# ProPrj_11_dc_2024-12-13.net
KiCad netlist of a schematic drawn in EasyEDA Pro
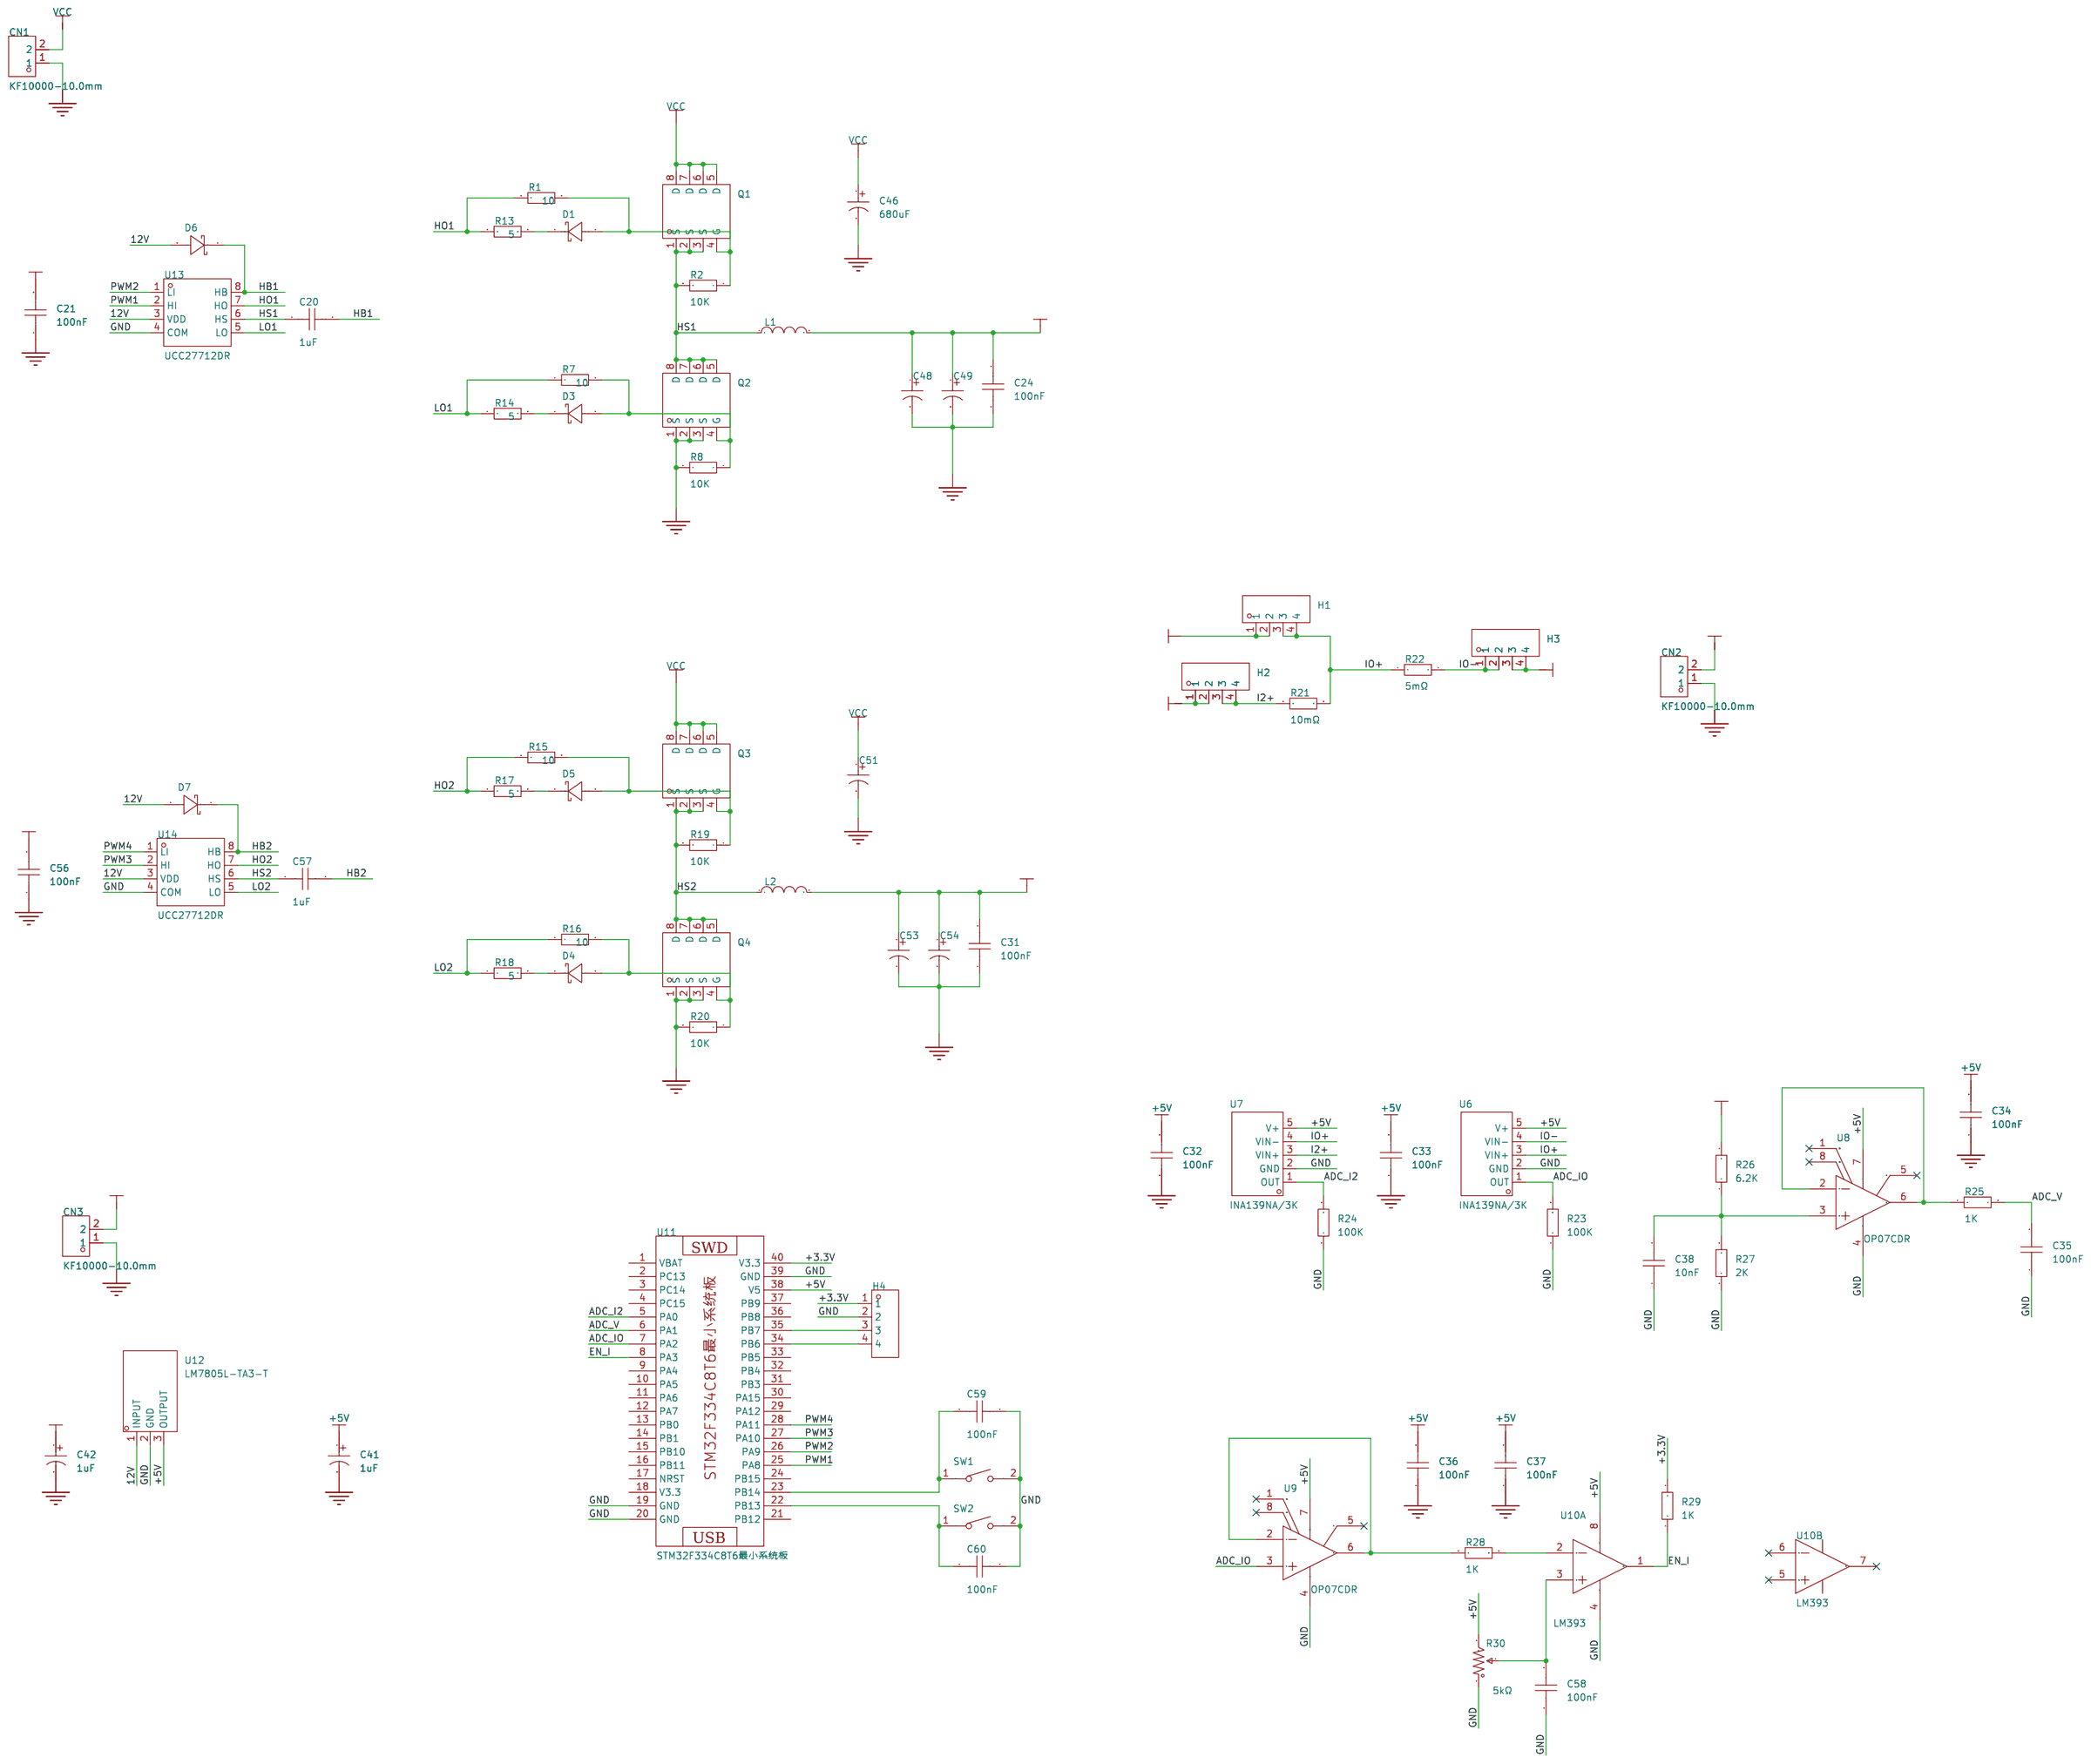
[diagram p0: schematic sheet]

(export (version "E")
  (design (tool "Eeschema 10.0.6"))
  (components
    (comp (ref "C20")
      (value "1uF")
      (footprint "easyedapro:C0603")
      (libsource (lib "easyedapro") (part "CapAcitance"))
    )
    (comp (ref "C21")
      (value "100nF")
      (footprint "easyedapro:C0603")
      (libsource (lib "easyedapro") (part "CapAcitance"))
    )
    (comp (ref "C24")
      (value "100nF")
      (footprint "easyedapro:C0603")
      (libsource (lib "easyedapro") (part "CapAcitance"))
    )
    (comp (ref "C31")
      (value "100nF")
      (footprint "easyedapro:C0603")
      (libsource (lib "easyedapro") (part "CapAcitance"))
    )
    (comp (ref "C32")
      (value "100nF")
      (footprint "easyedapro:C0603")
      (libsource (lib "easyedapro") (part "CapAcitance"))
    )
    (comp (ref "C33")
      (value "100nF")
      (footprint "easyedapro:C0603")
      (libsource (lib "easyedapro") (part "CapAcitance"))
    )
    (comp (ref "C34")
      (value "100nF")
      (footprint "easyedapro:C0603")
      (libsource (lib "easyedapro") (part "CapAcitance"))
    )
    (comp (ref "C35")
      (value "100nF")
      (footprint "easyedapro:C0603")
      (libsource (lib "easyedapro") (part "CapAcitance"))
    )
    (comp (ref "C36")
      (value "100nF")
      (footprint "easyedapro:C0603")
      (libsource (lib "easyedapro") (part "CapAcitance"))
    )
    (comp (ref "C37")
      (value "100nF")
      (footprint "easyedapro:C0603")
      (libsource (lib "easyedapro") (part "CapAcitance"))
    )
    (comp (ref "C38")
      (value "10nF")
      (footprint "easyedapro:C0603")
      (libsource (lib "easyedapro") (part "CapAcitance"))
    )
    (comp (ref "C41")
      (value "1uF")
      (footprint "easyedapro:CAP-TH_BD5.0-P2.00-D0.8-FD")
      (description "容值:1uF;精度:±20%;额定电压:50V;")
      (fields (field (name "Manufacturer Part") "KF010M050C110A") (field (name "Manufacturer") "CapXon(丰宾)"))
      (libsource (lib "easyedapro") (part "KF010M050C110A"))
    )
    (comp (ref "C42")
      (value "1uF")
      (footprint "easyedapro:CAP-TH_BD5.0-P2.00-D0.8-FD")
      (description "容值:1uF;精度:±20%;额定电压:50V;")
      (fields (field (name "Manufacturer Part") "KF010M050C110A") (field (name "Manufacturer") "CapXon(丰宾)"))
      (libsource (lib "easyedapro") (part "KF010M050C110A"))
    )
    (comp (ref "C46")
      (value "680uF")
      (footprint "easyedapro:CAP-TH_BD12.5-P5.00-D0.6-FD")
      (description "容值:680uF;精度:±20%;额定电压:63V;")
      (fields (field (name "Manufacturer Part") "ERR1JM681W25OT") (field (name "Manufacturer") "AISHI(艾华集团)"))
      (libsource (lib "easyedapro") (part "ERR1JM681W25OT"))
    )
    (comp (ref "C48")
      (value "680uF")
      (footprint "easyedapro:CAP-TH_BD12.5-P5.00-D0.6-FD")
      (description "容值:680uF;精度:±20%;额定电压:63V;")
      (fields (field (name "Manufacturer Part") "ERR1JM681W25OT") (field (name "Manufacturer") "AISHI(艾华集团)"))
      (libsource (lib "easyedapro") (part "ERR1JM681W25OT"))
    )
    (comp (ref "C49")
      (value "680uF")
      (footprint "easyedapro:CAP-TH_BD12.5-P5.00-D0.6-FD")
      (description "容值:680uF;精度:±20%;额定电压:63V;")
      (fields (field (name "Manufacturer Part") "ERR1JM681W25OT") (field (name "Manufacturer") "AISHI(艾华集团)"))
      (libsource (lib "easyedapro") (part "ERR1JM681W25OT"))
    )
    (comp (ref "C51")
      (value "680uF")
      (footprint "easyedapro:CAP-TH_BD12.5-P5.00-D0.6-FD")
      (description "容值:680uF;精度:±20%;额定电压:63V;")
      (fields (field (name "Manufacturer Part") "ERR1JM681W25OT") (field (name "Manufacturer") "AISHI(艾华集团)"))
      (libsource (lib "easyedapro") (part "ERR1JM681W25OT"))
    )
    (comp (ref "C53")
      (value "680uF")
      (footprint "easyedapro:CAP-TH_BD12.5-P5.00-D0.6-FD")
      (description "容值:680uF;精度:±20%;额定电压:63V;")
      (fields (field (name "Manufacturer Part") "ERR1JM681W25OT") (field (name "Manufacturer") "AISHI(艾华集团)"))
      (libsource (lib "easyedapro") (part "ERR1JM681W25OT"))
    )
    (comp (ref "C54")
      (value "680uF")
      (footprint "easyedapro:CAP-TH_BD12.5-P5.00-D0.6-FD")
      (description "容值:680uF;精度:±20%;额定电压:63V;")
      (fields (field (name "Manufacturer Part") "ERR1JM681W25OT") (field (name "Manufacturer") "AISHI(艾华集团)"))
      (libsource (lib "easyedapro") (part "ERR1JM681W25OT"))
    )
    (comp (ref "C56")
      (value "100nF")
      (footprint "easyedapro:C0603")
      (libsource (lib "easyedapro") (part "CapAcitance"))
    )
    (comp (ref "C57")
      (value "1uF")
      (footprint "easyedapro:C0603")
      (libsource (lib "easyedapro") (part "CapAcitance"))
    )
    (comp (ref "C58")
      (value "100nF")
      (footprint "easyedapro:C0603")
      (libsource (lib "easyedapro") (part "CapAcitance"))
    )
    (comp (ref "C59")
      (value "100nF")
      (footprint "easyedapro:C0603")
      (libsource (lib "easyedapro") (part "CapAcitance"))
    )
    (comp (ref "C60")
      (value "100nF")
      (footprint "easyedapro:C0603")
      (libsource (lib "easyedapro") (part "CapAcitance"))
    )
    (comp (ref "CN1")
      (value "KF10000-10.0mm")
      (footprint "easyedapro:CONN-TH_2P-P10.00_KF10000-10.0MM")
      (libsource (lib "easyedapro") (part "KF10000-10.0MM_C9900018859"))
    )
    (comp (ref "CN2")
      (value "KF10000-10.0mm")
      (footprint "easyedapro:CONN-TH_2P-P10.00_KF10000-10.0MM")
      (libsource (lib "easyedapro") (part "KF10000-10.0MM_C9900018859"))
    )
    (comp (ref "CN3")
      (value "KF10000-10.0mm")
      (footprint "easyedapro:CONN-TH_2P-P10.00_KF10000-10.0MM")
      (libsource (lib "easyedapro") (part "KF10000-10.0MM_C9900018859"))
    )
    (comp (ref "D1")
      (value "1N5819WS S4")
      (footprint "easyedapro:SOD-323_L1.6-W1.3-LS2.7-RD")
      (description "二极管配置:独立式;正向压降(Vf):600mV@200mA;直流反向耐压(Vr):40V;平均整流电流(Io):350mA;")
      (fields (field (name "Manufacturer") "JSMSEMI(杰盛微)"))
      (libsource (lib "easyedapro") (part "1N5819WS S4"))
    )
    (comp (ref "D3")
      (value "1N5819WS S4")
      (footprint "easyedapro:SOD-323_L1.6-W1.3-LS2.7-RD")
      (description "二极管配置:独立式;正向压降(Vf):600mV@200mA;直流反向耐压(Vr):40V;平均整流电流(Io):350mA;")
      (fields (field (name "Manufacturer") "JSMSEMI(杰盛微)"))
      (libsource (lib "easyedapro") (part "1N5819WS S4"))
    )
    (comp (ref "D4")
      (value "1N5819WS S4")
      (footprint "easyedapro:SOD-323_L1.6-W1.3-LS2.7-RD")
      (description "二极管配置:独立式;正向压降(Vf):600mV@200mA;直流反向耐压(Vr):40V;平均整流电流(Io):350mA;")
      (fields (field (name "Manufacturer") "JSMSEMI(杰盛微)"))
      (libsource (lib "easyedapro") (part "1N5819WS S4"))
    )
    (comp (ref "D5")
      (value "1N5819WS S4")
      (footprint "easyedapro:SOD-323_L1.6-W1.3-LS2.7-RD")
      (description "二极管配置:独立式;正向压降(Vf):600mV@200mA;直流反向耐压(Vr):40V;平均整流电流(Io):350mA;")
      (fields (field (name "Manufacturer") "JSMSEMI(杰盛微)"))
      (libsource (lib "easyedapro") (part "1N5819WS S4"))
    )
    (comp (ref "D6")
      (value "1N5819WS S4")
      (footprint "easyedapro:SOD-323_L1.6-W1.3-LS2.7-RD")
      (description "二极管配置:独立式;正向压降(Vf):600mV@200mA;直流反向耐压(Vr):40V;平均整流电流(Io):350mA;")
      (fields (field (name "Manufacturer") "JSMSEMI(杰盛微)"))
      (libsource (lib "easyedapro") (part "1N5819WS S4"))
    )
    (comp (ref "D7")
      (value "1N5819WS S4")
      (footprint "easyedapro:SOD-323_L1.6-W1.3-LS2.7-RD")
      (description "二极管配置:独立式;正向压降(Vf):600mV@200mA;直流反向耐压(Vr):40V;平均整流电流(Io):350mA;")
      (fields (field (name "Manufacturer") "JSMSEMI(杰盛微)"))
      (libsource (lib "easyedapro") (part "1N5819WS S4"))
    )
    (comp (ref "H1")
      (value "~")
      (footprint "easyedapro:HDR-TH_4P-P2.54-V-M")
      (libsource (lib "easyedapro") (part "PZ254V-11-04P"))
    )
    (comp (ref "H2")
      (value "~")
      (footprint "easyedapro:HDR-TH_4P-P2.54-V-M")
      (libsource (lib "easyedapro") (part "PZ254V-11-04P"))
    )
    (comp (ref "H3")
      (value "~")
      (footprint "easyedapro:HDR-TH_4P-P2.54-V-M")
      (libsource (lib "easyedapro") (part "PZ254V-11-04P"))
    )
    (comp (ref "H4")
      (value "~")
      (footprint "easyedapro:HDR-TH_4P-P2.54-V-M")
      (libsource (lib "easyedapro") (part "PZ254V-11-04P"))
    )
    (comp (ref "L1")
      (value "L-SMD1010-PCB")
      (footprint "easyedapro:IND-SMD_L10.0-W10.0-2")
      (libsource (lib "easyedapro") (part "L-SMD1010-PCB_C9900024506"))
    )
    (comp (ref "L2")
      (value "L-SMD1010-PCB")
      (footprint "easyedapro:IND-SMD_L10.0-W10.0-2")
      (libsource (lib "easyedapro") (part "L-SMD1010-PCB_C9900024506"))
    )
    (comp (ref "Q1")
      (value "CSD18540Q5BT")
      (footprint "easyedapro:PDFNWB-8L_L6.0-W5.0-P1.27-BL-EP")
      (description "60V、N 通道 NexFET&#153; 功率 MOSFET 8-VSON-CLIP -55 to 175")
      (fields (field (name "Manufacturer") "TI(德州仪器)"))
      (libsource (lib "easyedapro") (part "CSD18540Q5BT"))
    )
    (comp (ref "Q2")
      (value "CSD18540Q5BT")
      (footprint "easyedapro:PDFNWB-8L_L6.0-W5.0-P1.27-BL-EP")
      (description "60V、N 通道 NexFET&#153; 功率 MOSFET 8-VSON-CLIP -55 to 175")
      (fields (field (name "Manufacturer") "TI(德州仪器)"))
      (libsource (lib "easyedapro") (part "CSD18540Q5BT"))
    )
    (comp (ref "Q3")
      (value "CSD18540Q5BT")
      (footprint "easyedapro:PDFNWB-8L_L6.0-W5.0-P1.27-BL-EP")
      (description "60V、N 通道 NexFET&#153; 功率 MOSFET 8-VSON-CLIP -55 to 175")
      (fields (field (name "Manufacturer") "TI(德州仪器)"))
      (libsource (lib "easyedapro") (part "CSD18540Q5BT"))
    )
    (comp (ref "Q4")
      (value "CSD18540Q5BT")
      (footprint "easyedapro:PDFNWB-8L_L6.0-W5.0-P1.27-BL-EP")
      (description "60V、N 通道 NexFET&#153; 功率 MOSFET 8-VSON-CLIP -55 to 175")
      (fields (field (name "Manufacturer") "TI(德州仪器)"))
      (libsource (lib "easyedapro") (part "CSD18540Q5BT"))
    )
    (comp (ref "R1") (value "10") (footprint "easyedapro:R1206") (libsource (lib "easyedapro") (part "电阻")))
    (comp (ref "R2") (value "10K") (footprint "easyedapro:R1206") (libsource (lib "easyedapro") (part "电阻")))
    (comp (ref "R7") (value "10") (footprint "easyedapro:R1206") (libsource (lib "easyedapro") (part "电阻")))
    (comp (ref "R8") (value "10K") (footprint "easyedapro:R1206") (libsource (lib "easyedapro") (part "电阻")))
    (comp (ref "R13") (value "5") (footprint "easyedapro:R1206") (libsource (lib "easyedapro") (part "电阻")))
    (comp (ref "R14") (value "5") (footprint "easyedapro:R1206") (libsource (lib "easyedapro") (part "电阻")))
    (comp (ref "R15") (value "10") (footprint "easyedapro:R1206") (libsource (lib "easyedapro") (part "电阻")))
    (comp (ref "R16") (value "10") (footprint "easyedapro:R1206") (libsource (lib "easyedapro") (part "电阻")))
    (comp (ref "R17") (value "5") (footprint "easyedapro:R1206") (libsource (lib "easyedapro") (part "电阻")))
    (comp (ref "R18") (value "5") (footprint "easyedapro:R1206") (libsource (lib "easyedapro") (part "电阻")))
    (comp (ref "R19") (value "10K") (footprint "easyedapro:R1206") (libsource (lib "easyedapro") (part "电阻")))
    (comp (ref "R20") (value "10K") (footprint "easyedapro:R1206") (libsource (lib "easyedapro") (part "电阻")))
    (comp (ref "R21")
      (value "10mΩ")
      (footprint "easyedapro:R1206")
      (libsource (lib "easyedapro") (part "电阻"))
    )
    (comp (ref "R22") (value "5mΩ") (footprint "easyedapro:R1206") (libsource (lib "easyedapro") (part "电阻")))
    (comp (ref "R23")
      (value "100K")
      (footprint "easyedapro:R1206")
      (libsource (lib "easyedapro") (part "电阻"))
    )
    (comp (ref "R24")
      (value "100K")
      (footprint "easyedapro:R1206")
      (libsource (lib "easyedapro") (part "电阻"))
    )
    (comp (ref "R25") (value "1K") (footprint "easyedapro:R1206") (libsource (lib "easyedapro") (part "电阻")))
    (comp (ref "R26")
      (value "6.2K")
      (footprint "easyedapro:R1206")
      (libsource (lib "easyedapro") (part "电阻"))
    )
    (comp (ref "R27") (value "2K") (footprint "easyedapro:R1206") (libsource (lib "easyedapro") (part "电阻")))
    (comp (ref "R28") (value "1K") (footprint "easyedapro:R1206") (libsource (lib "easyedapro") (part "电阻")))
    (comp (ref "R29") (value "1K") (footprint "easyedapro:R1206") (libsource (lib "easyedapro") (part "电阻")))
    (comp (ref "R30")
      (value "5kΩ")
      (footprint "easyedapro:RES-ADJ-TH_3P-L9.5-W4.85-P2.50-BL-BS")
      (description "阻值:5kΩ;精度:±10%;")
      (fields (field (name "Manufacturer Part") "3296W-1-502") (field (name "Manufacturer") "BOCHEN(博晨)"))
      (libsource (lib "easyedapro") (part "3296W-1-502"))
    )
    (comp (ref "SW1")
      (value "轻触按键3*4*H")
      (footprint "easyedapro:SW-SMD_L4.0-W2.9-LS5.0")
      (libsource (lib "easyedapro") (part "轻触按键3*4*H"))
    )
    (comp (ref "SW2")
      (value "轻触按键3*4*H")
      (footprint "easyedapro:SW-SMD_L4.0-W2.9-LS5.0")
      (libsource (lib "easyedapro") (part "轻触按键3*4*H"))
    )
    (comp (ref "U6")
      (value "INA139NA/3K")
      (footprint "easyedapro:SOT-23-5_L3.0-W1.7-P0.95-LS2.8-BR")
      (description "INA139 36V、高侧、高速、电流输出电流分流监控器")
      (fields (field (name "Manufacturer") "TI(德州仪器)"))
      (libsource (lib "easyedapro") (part "INA139NA/3K"))
    )
    (comp (ref "U7")
      (value "INA139NA/3K")
      (footprint "easyedapro:SOT-23-5_L3.0-W1.7-P0.95-LS2.8-BR")
      (description "INA139 36V、高侧、高速、电流输出电流分流监控器")
      (fields (field (name "Manufacturer") "TI(德州仪器)"))
      (libsource (lib "easyedapro") (part "INA139NA/3K"))
    )
    (comp (ref "U8")
      (value "OP07CDR")
      (footprint "easyedapro:SOIC-8_L4.9-W3.9-P1.27-LS6.0-BL")
      (description "放大器数:单路;增益带宽积(GBP):600kHz;输入偏置电流(Ib):1.8nA;压摆率(SR):0.3V/us;轨到轨:-;")
      (fields (field (name "Manufacturer") "TI(德州仪器)"))
      (libsource (lib "easyedapro") (part "OP07CDR"))
    )
    (comp (ref "U9")
      (value "OP07CDR")
      (footprint "easyedapro:SOIC-8_L4.9-W3.9-P1.27-LS6.0-BL")
      (description "放大器数:单路;增益带宽积(GBP):600kHz;输入偏置电流(Ib):1.8nA;压摆率(SR):0.3V/us;轨到轨:-;")
      (fields (field (name "Manufacturer") "TI(德州仪器)"))
      (libsource (lib "easyedapro") (part "OP07CDR"))
    )
    (comp (ref "U10")
      (value "LM393")
      (footprint "easyedapro:SOP-8_L4.9-W3.9-P1.27-LS6.0-BL")
      (description "输入失调电压(Vos):3mV;输入偏置电流(Ib):-;轨到轨:-;")
      (fields (field (name "Manufacturer") "IDCHIP(英锐芯)"))
      (libsource (lib "easyedapro") (part "LM393_C400839"))
    )
    (comp (ref "U11")
      (value "STM32F334C8T6最小系统板")
      (footprint "easyedapro:STM32F103C8T6核心板")
      (fields (field (name "Manufacturer Part") "STM32F103C8T6最小系统模块") (field (name "Manufacturer") "无"))
      (libsource (lib "easyedapro") (part "STM32F103C8T6最小系统板"))
    )
    (comp (ref "U12")
      (value "LM7805L-TA3-T")
      (footprint "easyedapro:TO-220IS_L10.16-W4.7-P2.54-L")
      (description "输出类型:-;")
      (libsource (lib "easyedapro") (part "LM7805L-TA3-T_C340686"))
    )
    (comp (ref "U13")
      (value "UCC27712DR")
      (footprint "easyedapro:SOIC-8_L4.9-W3.9-P1.27-LS6.0-BL")
      (description "驱动配置:半桥;负载类型:MOSFET；IGBT;驱动通道数:2;峰值灌电流:2.8A;峰值拉电流:1.8A;电源电压:10V~20V;上升时间:16ns;下降时间:10ns;")
      (fields (field (name "Manufacturer") "TI(德州仪器)"))
      (libsource (lib "easyedapro") (part "UCC27712DR"))
    )
    (comp (ref "U14")
      (value "UCC27712DR")
      (footprint "easyedapro:SOIC-8_L4.9-W3.9-P1.27-LS6.0-BL")
      (description "驱动配置:半桥;负载类型:MOSFET；IGBT;驱动通道数:2;峰值灌电流:2.8A;峰值拉电流:1.8A;电源电压:10V~20V;上升时间:16ns;下降时间:10ns;")
      (fields (field (name "Manufacturer") "TI(德州仪器)"))
      (libsource (lib "easyedapro") (part "UCC27712DR"))
    )
  )
  (nets
    (net (code "1") (name "+5V") (class "Default")
      (node (ref "C32") (pin "2") (pinfunction "2_2") (pintype "input"))
      (node (ref "C33") (pin "2") (pinfunction "2_2") (pintype "input"))
      (node (ref "C34") (pin "2") (pinfunction "2_2") (pintype "input"))
      (node (ref "C36") (pin "2") (pinfunction "2_2") (pintype "input"))
      (node (ref "C37") (pin "2") (pinfunction "2_2") (pintype "input"))
      (node (ref "C41") (pin "1") (pinfunction "1_1") (pintype "input"))
      (node (ref "R30") (pin "3") (pinfunction "3_3") (pintype "unspecified"))
      (node (ref "U10") (pin "8") (pinfunction "VCC_8") (pintype "unspecified"))
      (node (ref "U11") (pin "38") (pinfunction "V5_38") (pintype "input"))
      (node (ref "U12") (pin "3") (pinfunction "OUTPUT_3") (pintype "unspecified"))
      (node (ref "U6") (pin "5") (pinfunction "V+_5") (pintype "unspecified"))
      (node (ref "U7") (pin "5") (pinfunction "V+_5") (pintype "unspecified"))
      (node (ref "U8") (pin "7") (pinfunction "VCC+_7") (pintype "unspecified"))
      (node (ref "U9") (pin "7") (pinfunction "VCC+_7") (pintype "unspecified"))
    )
    (net (code "2") (name "/+3.3V") (class "Default")
      (node (ref "H4") (pin "1") (pinfunction "1_1") (pintype "unspecified"))
      (node (ref "R29") (pin "2") (pinfunction "2_2") (pintype "input"))
      (node (ref "U11") (pin "40") (pinfunction "V3.3_40") (pintype "input"))
    )
    (net (code "3") (name "/ADC_I2") (class "Default")
      (node (ref "R24") (pin "2") (pinfunction "2_2") (pintype "input"))
      (node (ref "U11") (pin "5") (pinfunction "PA0_5") (pintype "bidirectional"))
      (node (ref "U7") (pin "1") (pinfunction "OUT_1") (pintype "unspecified"))
    )
    (net (code "4") (name "/ADC_IO") (class "Default")
      (node (ref "R23") (pin "2") (pinfunction "2_2") (pintype "input"))
      (node (ref "U11") (pin "7") (pinfunction "PA2_7") (pintype "bidirectional"))
      (node (ref "U6") (pin "1") (pinfunction "OUT_1") (pintype "unspecified"))
      (node (ref "U9") (pin "3") (pinfunction "IN+_3") (pintype "unspecified"))
    )
    (net (code "5") (name "/ADC_V") (class "Default")
      (node (ref "C35") (pin "2") (pinfunction "2_2") (pintype "input"))
      (node (ref "R25") (pin "2") (pinfunction "2_2") (pintype "input"))
      (node (ref "U11") (pin "6") (pinfunction "PA1_6") (pintype "bidirectional"))
    )
    (net (code "6") (name "/EN_I") (class "Default")
      (node (ref "R29") (pin "1") (pinfunction "1_1") (pintype "input"))
      (node (ref "U10") (pin "1") (pinfunction "OUTA_1") (pintype "output"))
      (node (ref "U11") (pin "8") (pinfunction "PA3_8") (pintype "bidirectional"))
    )
    (net (code "7") (name "/HB1") (class "Default")
      (node (ref "C20") (pin "2") (pinfunction "2_2") (pintype "input"))
      (node (ref "D6") (pin "1") (pinfunction "C_1") (pintype "unspecified"))
      (node (ref "U13") (pin "8") (pinfunction "HB_8") (pintype "unspecified"))
    )
    (net (code "8") (name "/HB2") (class "Default")
      (node (ref "C57") (pin "2") (pinfunction "2_2") (pintype "input"))
      (node (ref "D7") (pin "1") (pinfunction "C_1") (pintype "unspecified"))
      (node (ref "U14") (pin "8") (pinfunction "HB_8") (pintype "unspecified"))
    )
    (net (code "9") (name "/HO1") (class "Default")
      (node (ref "R1") (pin "1") (pinfunction "1_1") (pintype "input"))
      (node (ref "R13") (pin "1") (pinfunction "1_1") (pintype "input"))
      (node (ref "U13") (pin "7") (pinfunction "HO_7") (pintype "unspecified"))
    )
    (net (code "10") (name "/HO2") (class "Default")
      (node (ref "R15") (pin "1") (pinfunction "1_1") (pintype "input"))
      (node (ref "R17") (pin "1") (pinfunction "1_1") (pintype "input"))
      (node (ref "U14") (pin "7") (pinfunction "HO_7") (pintype "unspecified"))
    )
    (net (code "11") (name "/HS1") (class "Default")
      (node (ref "C20") (pin "1") (pinfunction "1_1") (pintype "input"))
      (node (ref "L1") (pin "1") (pinfunction "1_1") (pintype "input"))
      (node (ref "Q1") (pin "1") (pinfunction "S_1") (pintype "input"))
      (node (ref "Q1") (pin "2") (pinfunction "S_2") (pintype "input"))
      (node (ref "Q1") (pin "3") (pinfunction "S_3") (pintype "input"))
      (node (ref "Q2") (pin "5") (pinfunction "D_5") (pintype "input"))
      (node (ref "Q2") (pin "6") (pinfunction "D_6") (pintype "input"))
      (node (ref "Q2") (pin "7") (pinfunction "D_7") (pintype "input"))
      (node (ref "Q2") (pin "8") (pinfunction "D_8") (pintype "input"))
      (node (ref "R2") (pin "2") (pinfunction "2_2") (pintype "input"))
      (node (ref "U13") (pin "6") (pinfunction "HS_6") (pintype "unspecified"))
    )
    (net (code "12") (name "/HS2") (class "Default")
      (node (ref "C57") (pin "1") (pinfunction "1_1") (pintype "input"))
      (node (ref "L2") (pin "1") (pinfunction "1_1") (pintype "input"))
      (node (ref "Q3") (pin "1") (pinfunction "S_1") (pintype "input"))
      (node (ref "Q3") (pin "2") (pinfunction "S_2") (pintype "input"))
      (node (ref "Q3") (pin "3") (pinfunction "S_3") (pintype "input"))
      (node (ref "Q4") (pin "5") (pinfunction "D_5") (pintype "input"))
      (node (ref "Q4") (pin "6") (pinfunction "D_6") (pintype "input"))
      (node (ref "Q4") (pin "7") (pinfunction "D_7") (pintype "input"))
      (node (ref "Q4") (pin "8") (pinfunction "D_8") (pintype "input"))
      (node (ref "R19") (pin "2") (pinfunction "2_2") (pintype "input"))
      (node (ref "U14") (pin "6") (pinfunction "HS_6") (pintype "unspecified"))
    )
    (net (code "13") (name "/I2+") (class "Default")
      (node (ref "H2") (pin "3") (pinfunction "3_3") (pintype "unspecified"))
      (node (ref "H2") (pin "4") (pinfunction "4_4") (pintype "unspecified"))
      (node (ref "R21") (pin "1") (pinfunction "1_1") (pintype "input"))
      (node (ref "U7") (pin "3") (pinfunction "VIN+_3") (pintype "unspecified"))
    )
    (net (code "14") (name "/IO+") (class "Default")
      (node (ref "H1") (pin "3") (pinfunction "3_3") (pintype "unspecified"))
      (node (ref "H1") (pin "4") (pinfunction "4_4") (pintype "unspecified"))
      (node (ref "R21") (pin "2") (pinfunction "2_2") (pintype "input"))
      (node (ref "R22") (pin "1") (pinfunction "1_1") (pintype "input"))
      (node (ref "U6") (pin "3") (pinfunction "VIN+_3") (pintype "unspecified"))
      (node (ref "U7") (pin "4") (pinfunction "VIN-_4") (pintype "unspecified"))
    )
    (net (code "15") (name "/IO-") (class "Default")
      (node (ref "H3") (pin "1") (pinfunction "1_1") (pintype "unspecified"))
      (node (ref "H3") (pin "2") (pinfunction "2_2") (pintype "unspecified"))
      (node (ref "R22") (pin "2") (pinfunction "2_2") (pintype "input"))
      (node (ref "U6") (pin "4") (pinfunction "VIN-_4") (pintype "unspecified"))
    )
    (net (code "16") (name "/LO1") (class "Default")
      (node (ref "R14") (pin "1") (pinfunction "1_1") (pintype "input"))
      (node (ref "R7") (pin "1") (pinfunction "1_1") (pintype "input"))
      (node (ref "U13") (pin "5") (pinfunction "LO_5") (pintype "unspecified"))
    )
    (net (code "17") (name "/LO2") (class "Default")
      (node (ref "R16") (pin "1") (pinfunction "1_1") (pintype "input"))
      (node (ref "R18") (pin "1") (pinfunction "1_1") (pintype "input"))
      (node (ref "U14") (pin "5") (pinfunction "LO_5") (pintype "unspecified"))
    )
    (net (code "18") (name "/PWM1") (class "Default")
      (node (ref "U11") (pin "25") (pinfunction "PA8_25") (pintype "bidirectional"))
      (node (ref "U13") (pin "2") (pinfunction "HI_2") (pintype "unspecified"))
    )
    (net (code "19") (name "/PWM2") (class "Default")
      (node (ref "U11") (pin "26") (pinfunction "PA9_26") (pintype "bidirectional"))
      (node (ref "U13") (pin "1") (pinfunction "LI_1") (pintype "unspecified"))
    )
    (net (code "20") (name "/PWM3") (class "Default")
      (node (ref "U11") (pin "27") (pinfunction "PA10_27") (pintype "bidirectional"))
      (node (ref "U14") (pin "2") (pinfunction "HI_2") (pintype "unspecified"))
    )
    (net (code "21") (name "/PWM4") (class "Default")
      (node (ref "U11") (pin "28") (pinfunction "PA11_28") (pintype "bidirectional"))
      (node (ref "U14") (pin "1") (pinfunction "LI_1") (pintype "unspecified"))
    )
    (net (code "22") (name "12V") (class "Default")
      (node (ref "C21") (pin "2") (pinfunction "2_2") (pintype "input"))
      (node (ref "C42") (pin "1") (pinfunction "1_1") (pintype "input"))
      (node (ref "C56") (pin "2") (pinfunction "2_2") (pintype "input"))
      (node (ref "CN3") (pin "2") (pinfunction "2_2") (pintype "input"))
      (node (ref "D6") (pin "2") (pinfunction "A_2") (pintype "unspecified"))
      (node (ref "D7") (pin "2") (pinfunction "A_2") (pintype "unspecified"))
      (node (ref "U12") (pin "1") (pinfunction "INPUT_1") (pintype "unspecified"))
      (node (ref "U13") (pin "3") (pinfunction "VDD_3") (pintype "unspecified"))
      (node (ref "U14") (pin "3") (pinfunction "VDD_3") (pintype "unspecified"))
    )
    (net (code "23") (name "GND") (class "Default")
      (node (ref "C21") (pin "1") (pinfunction "1_1") (pintype "input"))
      (node (ref "C24") (pin "1") (pinfunction "1_1") (pintype "input"))
      (node (ref "C31") (pin "1") (pinfunction "1_1") (pintype "input"))
      (node (ref "C32") (pin "1") (pinfunction "1_1") (pintype "input"))
      (node (ref "C33") (pin "1") (pinfunction "1_1") (pintype "input"))
      (node (ref "C34") (pin "1") (pinfunction "1_1") (pintype "input"))
      (node (ref "C35") (pin "1") (pinfunction "1_1") (pintype "input"))
      (node (ref "C36") (pin "1") (pinfunction "1_1") (pintype "input"))
      (node (ref "C37") (pin "1") (pinfunction "1_1") (pintype "input"))
      (node (ref "C38") (pin "1") (pinfunction "1_1") (pintype "input"))
      (node (ref "C41") (pin "2") (pinfunction "2_2") (pintype "input"))
      (node (ref "C42") (pin "2") (pinfunction "2_2") (pintype "input"))
      (node (ref "C46") (pin "2") (pinfunction "2_2") (pintype "input"))
      (node (ref "C48") (pin "2") (pinfunction "2_2") (pintype "input"))
      (node (ref "C49") (pin "2") (pinfunction "2_2") (pintype "input"))
      (node (ref "C51") (pin "2") (pinfunction "2_2") (pintype "input"))
      (node (ref "C53") (pin "2") (pinfunction "2_2") (pintype "input"))
      (node (ref "C54") (pin "2") (pinfunction "2_2") (pintype "input"))
      (node (ref "C56") (pin "1") (pinfunction "1_1") (pintype "input"))
      (node (ref "C58") (pin "1") (pinfunction "1_1") (pintype "input"))
      (node (ref "C59") (pin "2") (pinfunction "2_2") (pintype "input"))
      (node (ref "C60") (pin "2") (pinfunction "2_2") (pintype "input"))
      (node (ref "CN1") (pin "1") (pinfunction "1_1") (pintype "input"))
      (node (ref "CN2") (pin "1") (pinfunction "1_1") (pintype "input"))
      (node (ref "CN3") (pin "1") (pinfunction "1_1") (pintype "input"))
      (node (ref "H4") (pin "2") (pinfunction "2_2") (pintype "unspecified"))
      (node (ref "Q2") (pin "1") (pinfunction "S_1") (pintype "input"))
      (node (ref "Q2") (pin "2") (pinfunction "S_2") (pintype "input"))
      (node (ref "Q2") (pin "3") (pinfunction "S_3") (pintype "input"))
      (node (ref "Q4") (pin "1") (pinfunction "S_1") (pintype "input"))
      (node (ref "Q4") (pin "2") (pinfunction "S_2") (pintype "input"))
      (node (ref "Q4") (pin "3") (pinfunction "S_3") (pintype "input"))
      (node (ref "R20") (pin "2") (pinfunction "2_2") (pintype "input"))
      (node (ref "R23") (pin "1") (pinfunction "1_1") (pintype "input"))
      (node (ref "R24") (pin "1") (pinfunction "1_1") (pintype "input"))
      (node (ref "R27") (pin "1") (pinfunction "1_1") (pintype "input"))
      (node (ref "R30") (pin "1") (pinfunction "1_1") (pintype "unspecified"))
      (node (ref "R8") (pin "2") (pinfunction "2_2") (pintype "input"))
      (node (ref "SW1") (pin "2") (pinfunction "2_2") (pintype "unspecified"))
      (node (ref "SW2") (pin "2") (pinfunction "2_2") (pintype "unspecified"))
      (node (ref "U10") (pin "4") (pinfunction "GND_4") (pintype "unspecified"))
      (node (ref "U11") (pin "19") (pinfunction "GND_19") (pintype "input"))
      (node (ref "U11") (pin "20") (pinfunction "GND_20") (pintype "input"))
      (node (ref "U11") (pin "39") (pinfunction "GND_39") (pintype "input"))
      (node (ref "U12") (pin "2") (pinfunction "GND_2") (pintype "unspecified"))
      (node (ref "U13") (pin "4") (pinfunction "COM_4") (pintype "unspecified"))
      (node (ref "U14") (pin "4") (pinfunction "COM_4") (pintype "unspecified"))
      (node (ref "U6") (pin "2") (pinfunction "GND_2") (pintype "unspecified"))
      (node (ref "U7") (pin "2") (pinfunction "GND_2") (pintype "unspecified"))
      (node (ref "U8") (pin "4") (pinfunction "VCC-_4") (pintype "unspecified"))
      (node (ref "U9") (pin "4") (pinfunction "VCC-_4") (pintype "unspecified"))
    )
    (net (code "24") (name "Net-(D1-A)") (class "Default")
      (node (ref "D1") (pin "2") (pinfunction "A_2") (pintype "unspecified"))
      (node (ref "Q1") (pin "4") (pinfunction "G_4") (pintype "input"))
      (node (ref "R1") (pin "2") (pinfunction "2_2") (pintype "input"))
      (node (ref "R2") (pin "1") (pinfunction "1_1") (pintype "input"))
    )
    (net (code "25") (name "Net-(D1-C)") (class "Default")
      (node (ref "D1") (pin "1") (pinfunction "C_1") (pintype "unspecified"))
      (node (ref "R13") (pin "2") (pinfunction "2_2") (pintype "input"))
    )
    (net (code "26") (name "Net-(D3-A)") (class "Default")
      (node (ref "D3") (pin "2") (pinfunction "A_2") (pintype "unspecified"))
      (node (ref "Q2") (pin "4") (pinfunction "G_4") (pintype "input"))
      (node (ref "R7") (pin "2") (pinfunction "2_2") (pintype "input"))
      (node (ref "R8") (pin "1") (pinfunction "1_1") (pintype "input"))
    )
    (net (code "27") (name "Net-(D3-C)") (class "Default")
      (node (ref "D3") (pin "1") (pinfunction "C_1") (pintype "unspecified"))
      (node (ref "R14") (pin "2") (pinfunction "2_2") (pintype "input"))
    )
    (net (code "28") (name "Net-(D4-A)") (class "Default")
      (node (ref "D4") (pin "2") (pinfunction "A_2") (pintype "unspecified"))
      (node (ref "Q4") (pin "4") (pinfunction "G_4") (pintype "input"))
      (node (ref "R16") (pin "2") (pinfunction "2_2") (pintype "input"))
      (node (ref "R20") (pin "1") (pinfunction "1_1") (pintype "input"))
    )
    (net (code "29") (name "Net-(D4-C)") (class "Default")
      (node (ref "D4") (pin "1") (pinfunction "C_1") (pintype "unspecified"))
      (node (ref "R18") (pin "2") (pinfunction "2_2") (pintype "input"))
    )
    (net (code "30") (name "Net-(D5-A)") (class "Default")
      (node (ref "D5") (pin "2") (pinfunction "A_2") (pintype "unspecified"))
      (node (ref "Q3") (pin "4") (pinfunction "G_4") (pintype "input"))
      (node (ref "R15") (pin "2") (pinfunction "2_2") (pintype "input"))
      (node (ref "R19") (pin "1") (pinfunction "1_1") (pintype "input"))
    )
    (net (code "31") (name "Net-(D5-C)") (class "Default")
      (node (ref "D5") (pin "1") (pinfunction "C_1") (pintype "unspecified"))
      (node (ref "R17") (pin "2") (pinfunction "2_2") (pintype "input"))
    )
    (net (code "32") (name "Net-(U8-IN+)") (class "Default")
      (node (ref "C38") (pin "2") (pinfunction "2_2") (pintype "input"))
      (node (ref "R26") (pin "1") (pinfunction "1_1") (pintype "input"))
      (node (ref "R27") (pin "2") (pinfunction "2_2") (pintype "input"))
      (node (ref "U8") (pin "3") (pinfunction "IN+_3") (pintype "unspecified"))
    )
    (net (code "33") (name "Net-(U8-IN-)") (class "Default")
      (node (ref "R25") (pin "1") (pinfunction "1_1") (pintype "input"))
      (node (ref "U8") (pin "2") (pinfunction "IN-_2") (pintype "unspecified"))
      (node (ref "U8") (pin "6") (pinfunction "OUT_6") (pintype "output"))
    )
    (net (code "34") (name "Net-(U9-IN-)") (class "Default")
      (node (ref "R28") (pin "1") (pinfunction "1_1") (pintype "input"))
      (node (ref "U9") (pin "2") (pinfunction "IN-_2") (pintype "unspecified"))
      (node (ref "U9") (pin "6") (pinfunction "OUT_6") (pintype "output"))
    )
    (net (code "35") (name "Net-(U10A-INA+)") (class "Default")
      (node (ref "C58") (pin "2") (pinfunction "2_2") (pintype "input"))
      (node (ref "R30") (pin "2") (pinfunction "2_2") (pintype "unspecified"))
      (node (ref "U10") (pin "3") (pinfunction "INA+_3") (pintype "unspecified"))
    )
    (net (code "36") (name "Net-(U10A-INA-)") (class "Default")
      (node (ref "R28") (pin "2") (pinfunction "2_2") (pintype "input"))
      (node (ref "U10") (pin "2") (pinfunction "INA-_2") (pintype "unspecified"))
    )
    (net (code "37") (name "Net-(U11-PB6)") (class "Default")
      (node (ref "H4") (pin "4") (pinfunction "4_4") (pintype "unspecified"))
      (node (ref "U11") (pin "34") (pinfunction "PB6_34") (pintype "bidirectional"))
    )
    (net (code "38") (name "Net-(U11-PB7)") (class "Default")
      (node (ref "H4") (pin "3") (pinfunction "3_3") (pintype "unspecified"))
      (node (ref "U11") (pin "35") (pinfunction "PB7_35") (pintype "bidirectional"))
    )
    (net (code "39") (name "Net-(U11-PB13)") (class "Default")
      (node (ref "C60") (pin "1") (pinfunction "1_1") (pintype "input"))
      (node (ref "SW2") (pin "1") (pinfunction "1_1") (pintype "unspecified"))
      (node (ref "U11") (pin "22") (pinfunction "PB13_22") (pintype "bidirectional"))
    )
    (net (code "40") (name "Net-(U11-PB14)") (class "Default")
      (node (ref "C59") (pin "1") (pinfunction "1_1") (pintype "input"))
      (node (ref "SW1") (pin "1") (pinfunction "1_1") (pintype "unspecified"))
      (node (ref "U11") (pin "23") (pinfunction "PB14_23") (pintype "bidirectional"))
    )
    (net (code "41") (name "OUT") (class "Default")
      (node (ref "CN2") (pin "2") (pinfunction "2_2") (pintype "input"))
      (node (ref "H3") (pin "3") (pinfunction "3_3") (pintype "unspecified"))
      (node (ref "H3") (pin "4") (pinfunction "4_4") (pintype "unspecified"))
      (node (ref "R26") (pin "2") (pinfunction "2_2") (pintype "input"))
    )
    (net (code "42") (name "OUT1") (class "Default")
      (node (ref "C24") (pin "2") (pinfunction "2_2") (pintype "input"))
      (node (ref "C48") (pin "1") (pinfunction "1_1") (pintype "input"))
      (node (ref "C49") (pin "1") (pinfunction "1_1") (pintype "input"))
      (node (ref "H1") (pin "1") (pinfunction "1_1") (pintype "unspecified"))
      (node (ref "H1") (pin "2") (pinfunction "2_2") (pintype "unspecified"))
      (node (ref "L1") (pin "2") (pinfunction "2_2") (pintype "input"))
    )
    (net (code "43") (name "OUT2") (class "Default")
      (node (ref "C31") (pin "2") (pinfunction "2_2") (pintype "input"))
      (node (ref "C53") (pin "1") (pinfunction "1_1") (pintype "input"))
      (node (ref "C54") (pin "1") (pinfunction "1_1") (pintype "input"))
      (node (ref "H2") (pin "1") (pinfunction "1_1") (pintype "unspecified"))
      (node (ref "H2") (pin "2") (pinfunction "2_2") (pintype "unspecified"))
      (node (ref "L2") (pin "2") (pinfunction "2_2") (pintype "input"))
    )
    (net (code "44") (name "VCC") (class "Default")
      (node (ref "C46") (pin "1") (pinfunction "1_1") (pintype "input"))
      (node (ref "C51") (pin "1") (pinfunction "1_1") (pintype "input"))
      (node (ref "CN1") (pin "2") (pinfunction "2_2") (pintype "input"))
      (node (ref "Q1") (pin "5") (pinfunction "D_5") (pintype "input"))
      (node (ref "Q1") (pin "6") (pinfunction "D_6") (pintype "input"))
      (node (ref "Q1") (pin "7") (pinfunction "D_7") (pintype "input"))
      (node (ref "Q1") (pin "8") (pinfunction "D_8") (pintype "input"))
      (node (ref "Q3") (pin "5") (pinfunction "D_5") (pintype "input"))
      (node (ref "Q3") (pin "6") (pinfunction "D_6") (pintype "input"))
      (node (ref "Q3") (pin "7") (pinfunction "D_7") (pintype "input"))
      (node (ref "Q3") (pin "8") (pinfunction "D_8") (pintype "input"))
    )
    (net (code "45") (name "unconnected-(U8-NC-Pad5)") (class "Default")
      (node (ref "U8") (pin "5") (pinfunction "NC_5") (pintype "unspecified+no_connect"))
    )
    (net (code "46") (name "unconnected-(U8-OFFSET_N1-Pad1)") (class "Default")
      (node (ref "U8") (pin "1") (pinfunction "OFFSET_N1_1") (pintype "unspecified+no_connect"))
    )
    (net (code "47") (name "unconnected-(U8-OFFSET_N2-Pad8)") (class "Default")
      (node (ref "U8") (pin "8") (pinfunction "OFFSET_N2_8") (pintype "unspecified+no_connect"))
    )
    (net (code "48") (name "unconnected-(U9-NC-Pad5)") (class "Default")
      (node (ref "U9") (pin "5") (pinfunction "NC_5") (pintype "unspecified+no_connect"))
    )
    (net (code "49") (name "unconnected-(U9-OFFSET_N1-Pad1)") (class "Default")
      (node (ref "U9") (pin "1") (pinfunction "OFFSET_N1_1") (pintype "unspecified+no_connect"))
    )
    (net (code "50") (name "unconnected-(U9-OFFSET_N2-Pad8)") (class "Default")
      (node (ref "U9") (pin "8") (pinfunction "OFFSET_N2_8") (pintype "unspecified+no_connect"))
    )
    (net (code "51") (name "unconnected-(U10B-INB+-Pad5)") (class "Default")
      (node (ref "U10") (pin "5") (pinfunction "INB+_5") (pintype "unspecified+no_connect"))
    )
    (net (code "52") (name "unconnected-(U10B-INB--Pad6)") (class "Default")
      (node (ref "U10") (pin "6") (pinfunction "INB-_6") (pintype "unspecified+no_connect"))
    )
    (net (code "53") (name "unconnected-(U10B-OUTB-Pad7)") (class "Default")
      (node (ref "U10") (pin "7") (pinfunction "OUTB_7") (pintype "output+no_connect"))
    )
    (net (code "54") (name "unconnected-(U11-NRST-Pad17)") (class "Default")
      (node (ref "U11") (pin "17") (pinfunction "NRST_17") (pintype "bidirectional"))
    )
    (net (code "55") (name "unconnected-(U11-PA4-Pad9)") (class "Default")
      (node (ref "U11") (pin "9") (pinfunction "PA4_9") (pintype "bidirectional"))
    )
    (net (code "56") (name "unconnected-(U11-PA5-Pad10)") (class "Default")
      (node (ref "U11") (pin "10") (pinfunction "PA5_10") (pintype "bidirectional"))
    )
    (net (code "57") (name "unconnected-(U11-PA6-Pad11)") (class "Default")
      (node (ref "U11") (pin "11") (pinfunction "PA6_11") (pintype "bidirectional"))
    )
    (net (code "58") (name "unconnected-(U11-PA7-Pad12)") (class "Default")
      (node (ref "U11") (pin "12") (pinfunction "PA7_12") (pintype "bidirectional"))
    )
    (net (code "59") (name "unconnected-(U11-PA12-Pad29)") (class "Default")
      (node (ref "U11") (pin "29") (pinfunction "PA12_29") (pintype "bidirectional"))
    )
    (net (code "60") (name "unconnected-(U11-PA15-Pad30)") (class "Default")
      (node (ref "U11") (pin "30") (pinfunction "PA15_30") (pintype "bidirectional"))
    )
    (net (code "61") (name "unconnected-(U11-PB0-Pad13)") (class "Default")
      (node (ref "U11") (pin "13") (pinfunction "PB0_13") (pintype "bidirectional"))
    )
    (net (code "62") (name "unconnected-(U11-PB1-Pad14)") (class "Default")
      (node (ref "U11") (pin "14") (pinfunction "PB1_14") (pintype "bidirectional"))
    )
    (net (code "63") (name "unconnected-(U11-PB3-Pad31)") (class "Default")
      (node (ref "U11") (pin "31") (pinfunction "PB3_31") (pintype "bidirectional"))
    )
    (net (code "64") (name "unconnected-(U11-PB4-Pad32)") (class "Default")
      (node (ref "U11") (pin "32") (pinfunction "PB4_32") (pintype "bidirectional"))
    )
    (net (code "65") (name "unconnected-(U11-PB5-Pad33)") (class "Default")
      (node (ref "U11") (pin "33") (pinfunction "PB5_33") (pintype "bidirectional"))
    )
    (net (code "66") (name "unconnected-(U11-PB8-Pad36)") (class "Default")
      (node (ref "U11") (pin "36") (pinfunction "PB8_36") (pintype "bidirectional"))
    )
    (net (code "67") (name "unconnected-(U11-PB9-Pad37)") (class "Default")
      (node (ref "U11") (pin "37") (pinfunction "PB9_37") (pintype "bidirectional"))
    )
    (net (code "68") (name "unconnected-(U11-PB10-Pad15)") (class "Default")
      (node (ref "U11") (pin "15") (pinfunction "PB10_15") (pintype "bidirectional"))
    )
    (net (code "69") (name "unconnected-(U11-PB11-Pad16)") (class "Default")
      (node (ref "U11") (pin "16") (pinfunction "PB11_16") (pintype "bidirectional"))
    )
    (net (code "70") (name "unconnected-(U11-PB12-Pad21)") (class "Default")
      (node (ref "U11") (pin "21") (pinfunction "PB12_21") (pintype "bidirectional"))
    )
    (net (code "71") (name "unconnected-(U11-PB15-Pad24)") (class "Default")
      (node (ref "U11") (pin "24") (pinfunction "PB15_24") (pintype "bidirectional"))
    )
    (net (code "72") (name "unconnected-(U11-PC13-Pad2)") (class "Default")
      (node (ref "U11") (pin "2") (pinfunction "PC13_2") (pintype "bidirectional"))
    )
    (net (code "73") (name "unconnected-(U11-PC14-Pad3)") (class "Default")
      (node (ref "U11") (pin "3") (pinfunction "PC14_3") (pintype "bidirectional"))
    )
    (net (code "74") (name "unconnected-(U11-PC15-Pad4)") (class "Default")
      (node (ref "U11") (pin "4") (pinfunction "PC15_4") (pintype "bidirectional"))
    )
    (net (code "75") (name "unconnected-(U11-V3.3-Pad18)") (class "Default")
      (node (ref "U11") (pin "18") (pinfunction "V3.3_18") (pintype "input"))
    )
    (net (code "76") (name "unconnected-(U11-VBAT-Pad1)") (class "Default")
      (node (ref "U11") (pin "1") (pinfunction "VBAT_1") (pintype "input"))
    )
  )
)
